# Adafruit_MCP4728.net
KiCad netlist of a schematic drawn in EAGLE
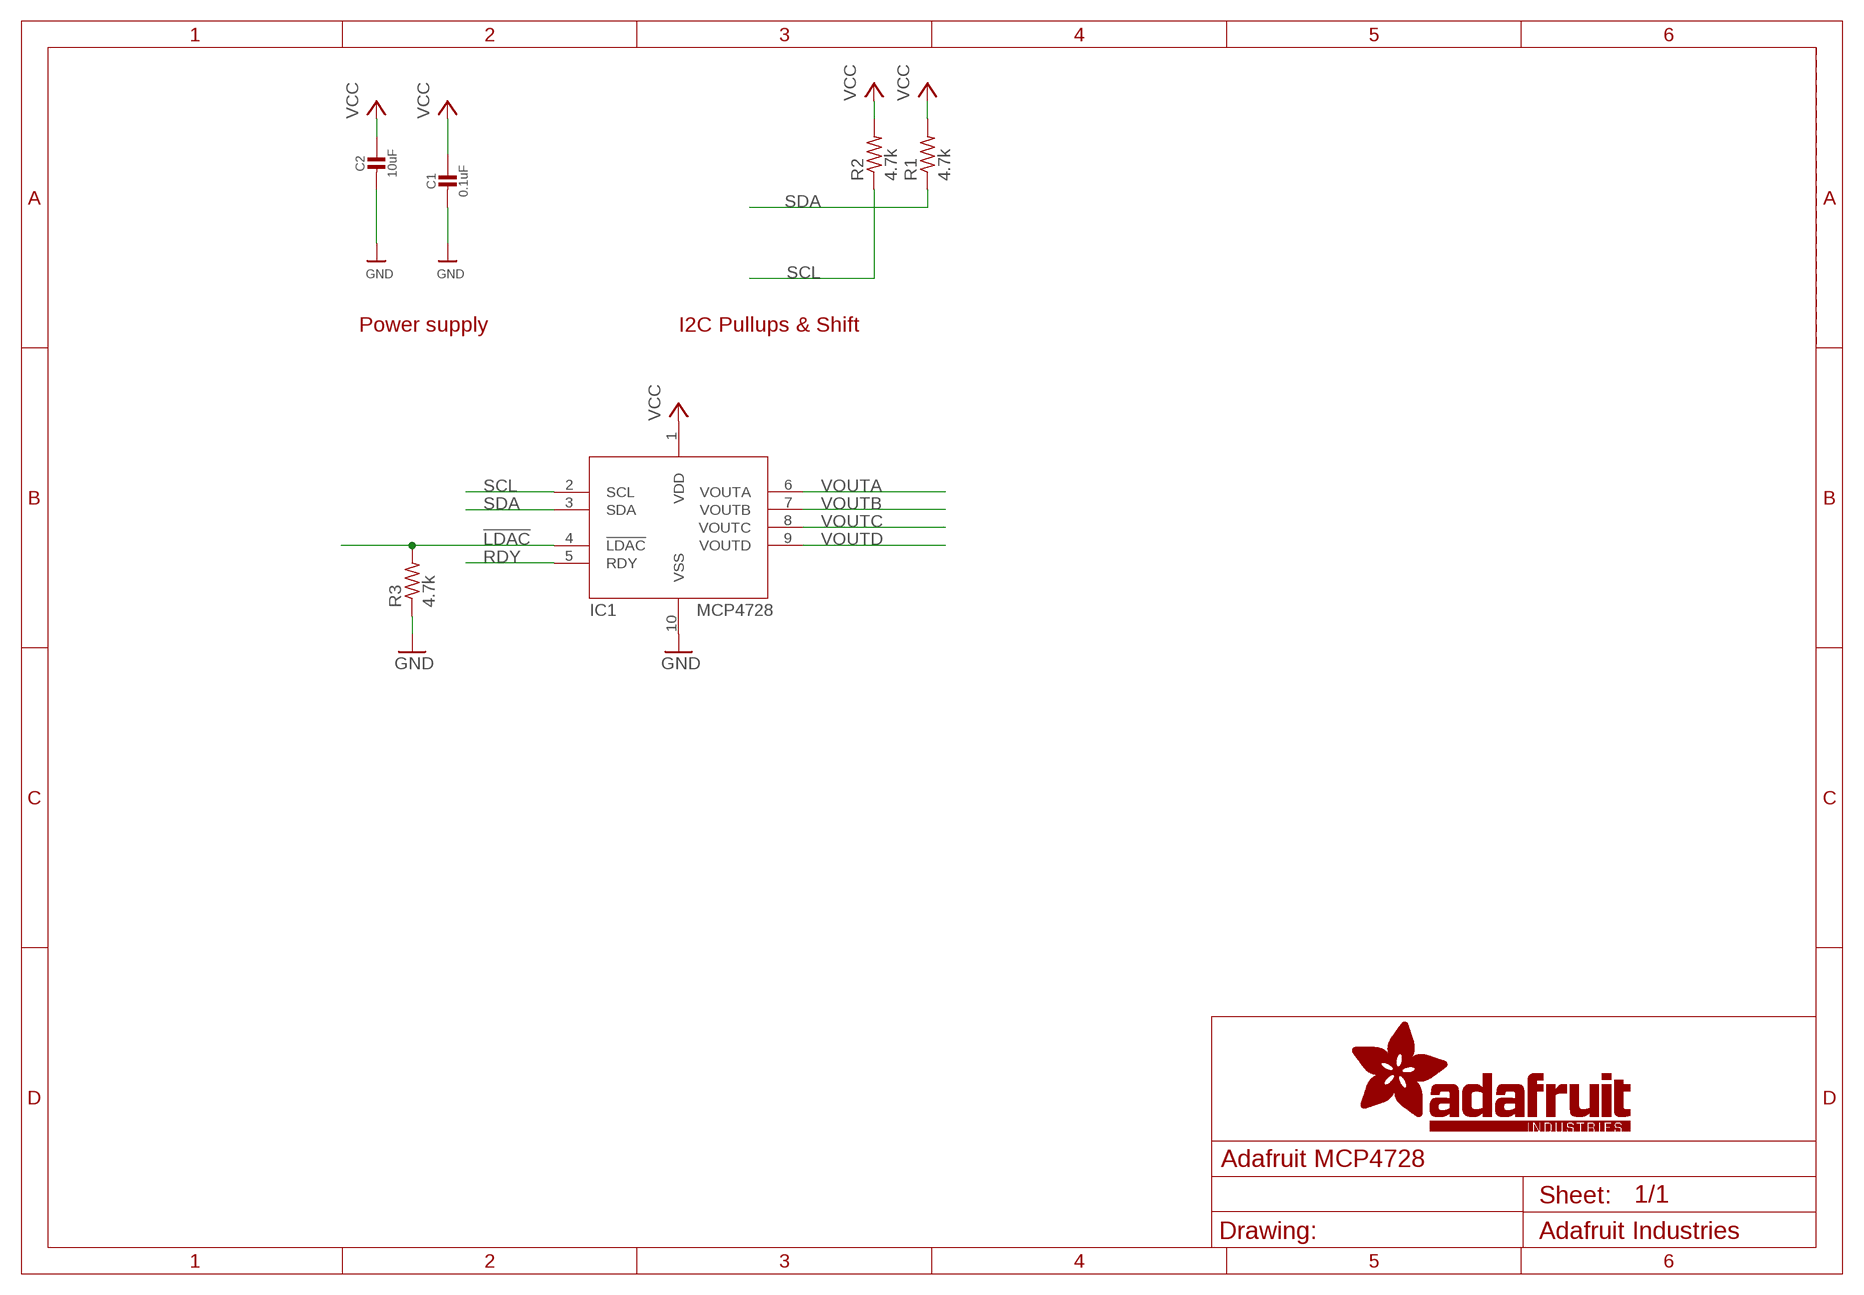
[diagram p0: schematic, sheet 1]

(export (version "E")
  (design (tool "Eeschema 10.0.6"))
  (components
    (comp (ref "C1")
      (value "0.1uF")
      (footprint "eagle-import:0603-NO")
      (libsource (lib "eagle-import") (part "CAP_CERAMIC0603_NO"))
    )
    (comp (ref "C2")
      (value "10uF")
      (footprint "eagle-import:0805-NO")
      (libsource (lib "eagle-import") (part "CAP_CERAMIC0805-NOOUTLINE"))
    )
    (comp (ref "IC1")
      (value "MCP4728")
      (footprint "eagle-import:MSOP10")
      (libsource (lib "eagle-import") (part "MCP4728"))
    )
    (comp (ref "R1")
      (value "4.7k")
      (footprint "eagle-import:0204_7")
      (libsource (lib "eagle-import") (part "R-US_0204/7"))
    )
    (comp (ref "R2")
      (value "4.7k")
      (footprint "eagle-import:0204_7")
      (libsource (lib "eagle-import") (part "R-US_0204/7"))
    )
    (comp (ref "R3")
      (value "4.7k")
      (footprint "eagle-import:0204_7")
      (libsource (lib "eagle-import") (part "R-US_0204/7"))
    )
  )
  (nets
    (net (code "1") (name "/RDY") (class "Default")
      (node (ref "IC1") (pin "5") (pinfunction "RDY_5") (pintype "output"))
    )
    (net (code "2") (name "/SCL") (class "Default")
      (node (ref "IC1") (pin "2") (pinfunction "SCL_2") (pintype "bidirectional"))
      (node (ref "R2") (pin "1") (pinfunction "1_1") (pintype "passive"))
    )
    (net (code "3") (name "/SDA") (class "Default")
      (node (ref "IC1") (pin "3") (pinfunction "SDA_3") (pintype "bidirectional"))
      (node (ref "R1") (pin "1") (pinfunction "1_1") (pintype "passive"))
    )
    (net (code "4") (name "/VOUTA") (class "Default")
      (node (ref "IC1") (pin "6") (pinfunction "VOUTA_6") (pintype "output"))
    )
    (net (code "5") (name "/VOUTB") (class "Default")
      (node (ref "IC1") (pin "7") (pinfunction "VOUTB_7") (pintype "output"))
    )
    (net (code "6") (name "/VOUTC") (class "Default")
      (node (ref "IC1") (pin "8") (pinfunction "VOUTC_8") (pintype "output"))
    )
    (net (code "7") (name "/VOUTD") (class "Default")
      (node (ref "IC1") (pin "9") (pinfunction "VOUTD_9") (pintype "output"))
    )
    (net (code "8") (name "/~{LDAC}") (class "Default")
      (node (ref "IC1") (pin "4") (pinfunction "~{LDAC}_4") (pintype "input"))
      (node (ref "R3") (pin "2") (pinfunction "2_2") (pintype "passive"))
    )
    (net (code "9") (name "GND") (class "Default")
      (node (ref "C1") (pin "2") (pinfunction "2_2") (pintype "passive"))
      (node (ref "C2") (pin "2") (pinfunction "2_2") (pintype "passive"))
      (node (ref "IC1") (pin "10") (pinfunction "VSS_10") (pintype "power_in"))
      (node (ref "R3") (pin "1") (pinfunction "1_1") (pintype "passive"))
    )
    (net (code "10") (name "VCC") (class "Default")
      (node (ref "C1") (pin "1") (pinfunction "1_1") (pintype "passive"))
      (node (ref "C2") (pin "1") (pinfunction "1_1") (pintype "passive"))
      (node (ref "IC1") (pin "1") (pinfunction "VDD_1") (pintype "power_in"))
      (node (ref "R1") (pin "2") (pinfunction "2_2") (pintype "passive"))
      (node (ref "R2") (pin "2") (pinfunction "2_2") (pintype "passive"))
    )
  )
)
